# AmpClickShematic.net
KiCad netlist of a schematic drawn in Altium Designer
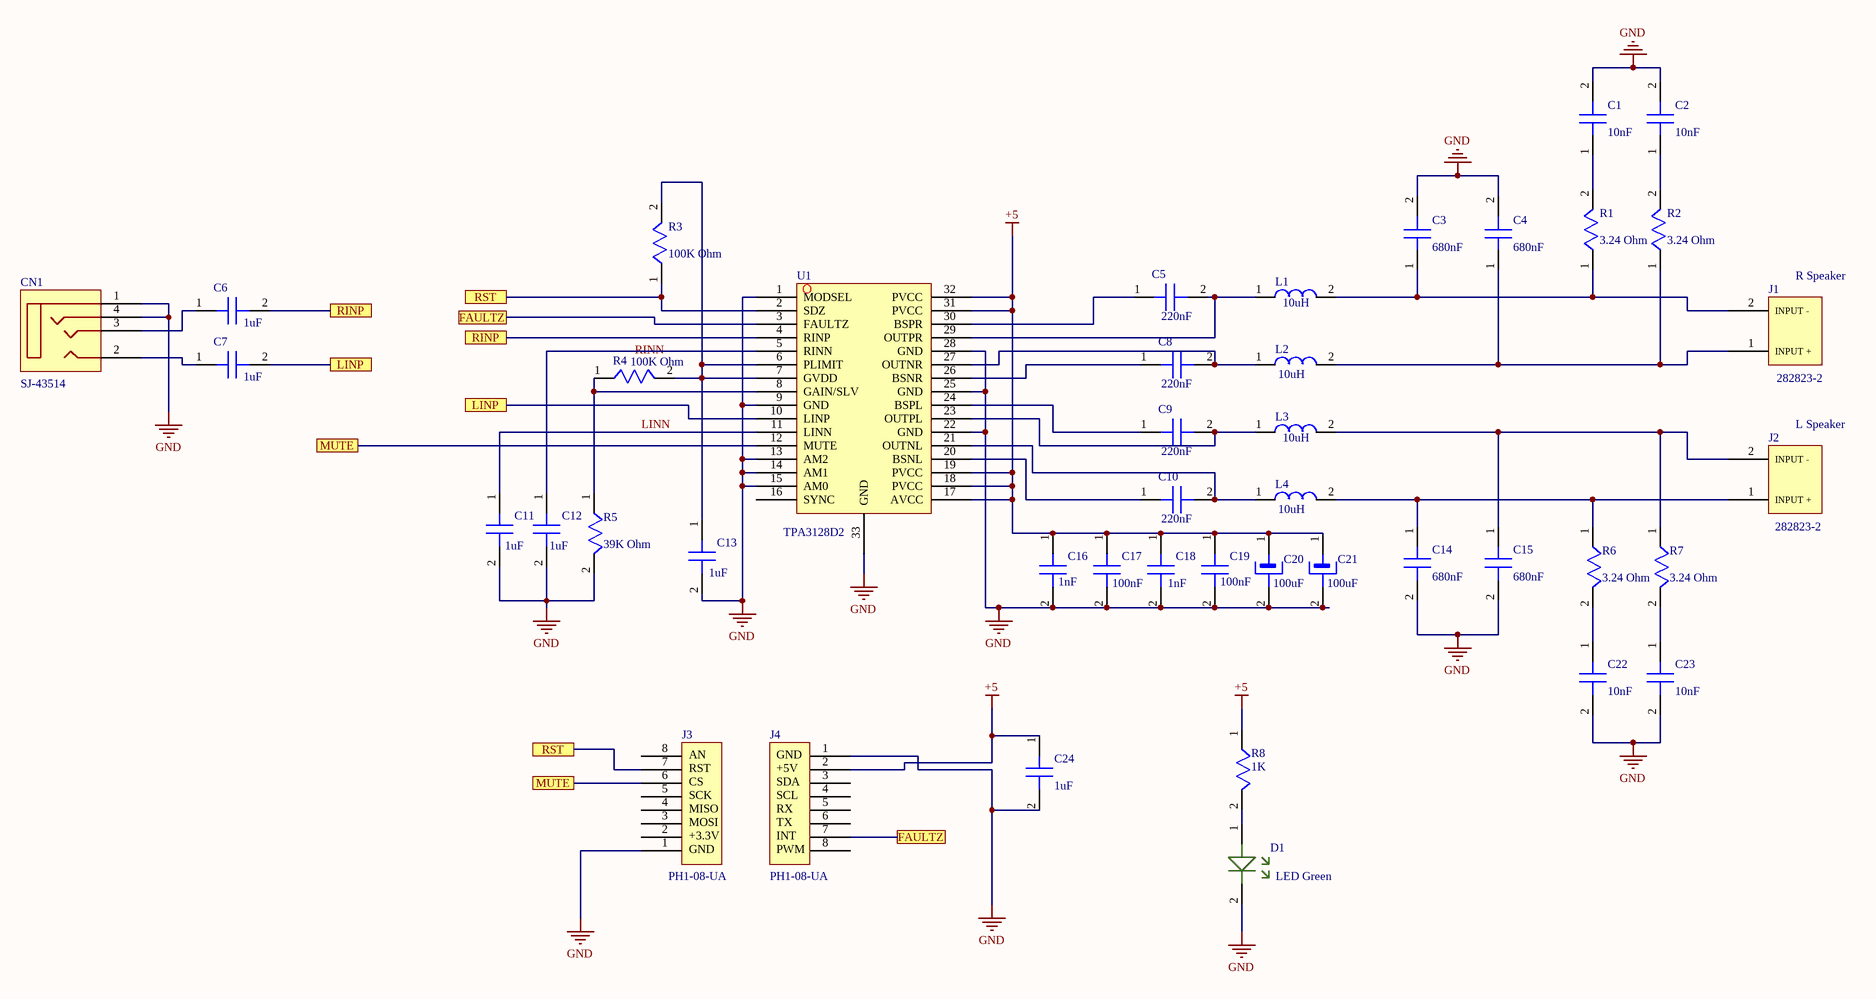
[diagram p0: AmpClickShematic.SchDoc]

(export (version "E")
  (design (tool "Eeschema 10.0.6"))
  (components
    (comp (ref "C1") (value "10nF") (footprint "CAP 10nF") (libsource (lib "AmpClick") (part "CAP 10nF")))
    (comp (ref "C2") (value "10nF") (footprint "CAP 10nF") (libsource (lib "AmpClick") (part "CAP 10nF")))
    (comp (ref "C3") (value "680nF") (footprint "CAP 680nF") (libsource (lib "AmpClick") (part "CAP 680nF")))
    (comp (ref "C4") (value "680nF") (footprint "CAP 680nF") (libsource (lib "AmpClick") (part "CAP 680nF")))
    (comp (ref "C5") (value "220nF") (footprint "CAP 220nF") (libsource (lib "AmpClick") (part "CAP 220nF")))
    (comp (ref "C6") (value "1uF") (footprint "CAP 1uF") (libsource (lib "AmpClick") (part "CAP 1uF")))
    (comp (ref "C7") (value "1uF") (footprint "CAP 1uF") (libsource (lib "AmpClick") (part "CAP 1uF")))
    (comp (ref "C8") (value "220nF") (footprint "CAP 220nF") (libsource (lib "AmpClick") (part "CAP 220nF")))
    (comp (ref "C9") (value "220nF") (footprint "CAP 220nF") (libsource (lib "AmpClick") (part "CAP 220nF")))
    (comp (ref "C10") (value "220nF") (footprint "CAP 220nF") (libsource (lib "AmpClick") (part "CAP 220nF")))
    (comp (ref "C11") (value "1uF") (footprint "CAP 1uF") (libsource (lib "AmpClick") (part "CAP 1uF")))
    (comp (ref "C12") (value "1uF") (footprint "CAP 1uF") (libsource (lib "AmpClick") (part "CAP 1uF")))
    (comp (ref "C13") (value "1uF") (footprint "CAP 1uF") (libsource (lib "AmpClick") (part "CAP 1uF")))
    (comp (ref "C14") (value "680nF") (footprint "CAP 680nF") (libsource (lib "AmpClick") (part "CAP 680nF")))
    (comp (ref "C15") (value "680nF") (footprint "CAP 680nF") (libsource (lib "AmpClick") (part "CAP 680nF")))
    (comp (ref "C16") (value "1nF") (footprint "CAP 1nF") (libsource (lib "AmpClick") (part "CAP 1nF")))
    (comp (ref "C17") (value "100nF") (footprint "CAP 100nF") (libsource (lib "AmpClick") (part "CAP 100nF")))
    (comp (ref "C18") (value "1nF") (footprint "CAP 1nF") (libsource (lib "AmpClick") (part "CAP 1nF")))
    (comp (ref "C19") (value "100nF") (footprint "CAP 100nF") (libsource (lib "AmpClick") (part "CAP 100nF")))
    (comp (ref "C20")
      (value "100uF")
      (footprint "CAP ALUM 100uF")
      (libsource (lib "AmpClick") (part "CAP ALUM 100uF"))
    )
    (comp (ref "C21")
      (value "100uF")
      (footprint "CAP ALUM 100uF")
      (libsource (lib "AmpClick") (part "CAP ALUM 100uF"))
    )
    (comp (ref "C22") (value "10nF") (footprint "CAP 10nF") (libsource (lib "AmpClick") (part "CAP 10nF")))
    (comp (ref "C23") (value "10nF") (footprint "CAP 10nF") (libsource (lib "AmpClick") (part "CAP 10nF")))
    (comp (ref "C24") (value "1uF") (footprint "CAP 1uF") (libsource (lib "AmpClick") (part "CAP 1uF")))
    (comp (ref "CN1")
      (value "Audio Jack")
      (footprint "Audio Jack")
      (fields (field (name "NAME") "SJ-43514"))
      (libsource (lib "AmpClick") (part "Audio Jack"))
    )
    (comp (ref "D1")
      (value "Green")
      (footprint "LED Green")
      (fields (field (name "NAME") "LED Green"))
      (libsource (lib "AmpClick") (part "LED Green"))
    )
    (comp (ref "J1")
      (value "R Speaker")
      (footprint "2P CONN 2.54mm")
      (fields (field (name "NAME") "282823-2"))
      (libsource (lib "AmpClick") (part "2P CONN"))
    )
    (comp (ref "J2")
      (value "L Speaker")
      (footprint "2P CONN 2.54mm")
      (fields (field (name "NAME") "282823-2"))
      (libsource (lib "AmpClick") (part "2P CONN"))
    )
    (comp (ref "J3")
      (value "8P HEADER")
      (footprint "8POS HEADER")
      (description "8 Position Header")
      (fields (field (name "NAME") "PH1-08-UA"))
      (libsource (lib "") (part "8P HEADER_1"))
    )
    (comp (ref "J4")
      (value "8P HEADER")
      (footprint "8POS HEADER")
      (description "8 Position Header")
      (fields (field (name "NAME") "PH1-08-UA"))
      (libsource (lib "AmpClick") (part "8P HEADER"))
    )
    (comp (ref "L1")
      (value "10uH")
      (footprint "Power Inductor")
      (fields (field (name "Comment") "Power Inductor 10uH"))
      (libsource (lib "AmpClick") (part "Power Inductor 10uH"))
    )
    (comp (ref "L2")
      (value "10uH")
      (footprint "Power Inductor")
      (fields (field (name "Comment") "Power Inductor 10uH"))
      (libsource (lib "AmpClick") (part "Power Inductor 10uH"))
    )
    (comp (ref "L3")
      (value "10uH")
      (footprint "Power Inductor")
      (fields (field (name "Comment") "Power Inductor 10uH"))
      (libsource (lib "AmpClick") (part "Power Inductor 10uH"))
    )
    (comp (ref "L4")
      (value "10uH")
      (footprint "Power Inductor")
      (fields (field (name "Comment") "Power Inductor 10uH"))
      (libsource (lib "AmpClick") (part "Power Inductor 10uH"))
    )
    (comp (ref "R1")
      (value "3.24 Ohm")
      (footprint "SMD RES 3.24ohm")
      (fields (field (name "Comment") "3.24ohm"))
      (libsource (lib "AmpClick") (part "SMD RES 3.24OHM"))
    )
    (comp (ref "R2")
      (value "3.24 Ohm")
      (footprint "SMD RES 3.24ohm")
      (fields (field (name "Comment") "3.24ohm"))
      (libsource (lib "AmpClick") (part "SMD RES 3.24OHM"))
    )
    (comp (ref "R3")
      (value "100K Ohm")
      (footprint "SMD RES 100K")
      (fields (field (name "Comment") "100K"))
      (libsource (lib "AmpClick") (part "SMD RES 100K"))
    )
    (comp (ref "R4")
      (value "100K Ohm")
      (footprint "SMD RES 100K")
      (fields (field (name "Comment") "100K"))
      (libsource (lib "AmpClick") (part "SMD RES 100K"))
    )
    (comp (ref "R5")
      (value "39K Ohm")
      (footprint "SMD RES 39K")
      (fields (field (name "Comment") "SMD RES 39K"))
      (libsource (lib "AmpClick") (part "SMD RES 39K"))
    )
    (comp (ref "R6")
      (value "3.24 Ohm")
      (footprint "SMD RES 3.24ohm")
      (fields (field (name "Comment") "3.24ohm"))
      (libsource (lib "AmpClick") (part "SMD RES 3.24OHM"))
    )
    (comp (ref "R7")
      (value "3.24 Ohm")
      (footprint "SMD RES 3.24ohm")
      (fields (field (name "Comment") "3.24ohm"))
      (libsource (lib "AmpClick") (part "SMD RES 3.24OHM"))
    )
    (comp (ref "R8") (value "1K") (footprint "SMD RES 1K") (libsource (lib "AmpClick") (part "SMD RES 1K")))
    (comp (ref "U1")
      (value "TPA 30W AMP.")
      (footprint "TPA 30W AMP.")
      (description "TPA 2x30W IC")
      (fields (field (name "NAME") "TPA3128D2"))
      (libsource (lib "AmpClick") (part "TPA 30W AMP."))
    )
  )
  (nets
    (net (code "1") (name "+5") (class "Default")
      (node (ref "C16") (pin "1") (pinfunction "PVCC_1") (pintype "passive"))
      (node (ref "C17") (pin "1") (pinfunction "PVCC_1") (pintype "passive"))
      (node (ref "C18") (pin "1") (pinfunction "PVCC_1") (pintype "passive"))
      (node (ref "C19") (pin "1") (pinfunction "PVCC_1") (pintype "passive"))
      (node (ref "C20") (pin "1") (pinfunction "PVCC_1") (pintype "passive"))
      (node (ref "C21") (pin "1") (pinfunction "PVCC_1") (pintype "passive"))
      (node (ref "C24") (pin "1") (pinfunction "PVCC_1") (pintype "passive"))
      (node (ref "J4") (pin "2") (pinfunction "6_2") (pintype "passive"))
      (node (ref "R8") (pin "1") (pinfunction "0_1") (pintype "passive"))
      (node (ref "U1") (pin "17") (pinfunction "AVCC_17") (pintype "passive"))
      (node (ref "U1") (pin "18") (pinfunction "PVCC_18") (pintype "passive"))
      (node (ref "U1") (pin "19") (pinfunction "PVCC_19") (pintype "passive"))
      (node (ref "U1") (pin "31") (pinfunction "PVCC_31") (pintype "passive"))
      (node (ref "U1") (pin "32") (pinfunction "PVCC_32") (pintype "passive"))
    )
    (net (code "2") (name "/FAULTZ") (class "Default")
      (node (ref "J4") (pin "7") (pinfunction "11_7") (pintype "passive"))
      (node (ref "U1") (pin "3") (pinfunction "FAULTZ_3") (pintype "passive"))
    )
    (net (code "3") (name "/LINP") (class "Default")
      (node (ref "C7") (pin "2") (pinfunction "PVCC_2") (pintype "passive"))
      (node (ref "U1") (pin "10") (pinfunction "LINP_10") (pintype "passive"))
    )
    (net (code "4") (name "/MUTE") (class "Default")
      (node (ref "J3") (pin "6") (pinfunction "10_6") (pintype "passive"))
      (node (ref "U1") (pin "12") (pinfunction "MUTE_12") (pintype "passive"))
    )
    (net (code "5") (name "/RINP") (class "Default")
      (node (ref "C6") (pin "2") (pinfunction "PVCC_2") (pintype "passive"))
      (node (ref "U1") (pin "4") (pinfunction "RINP_4") (pintype "passive"))
    )
    (net (code "6") (name "/RST") (class "Default")
      (node (ref "J3") (pin "7") (pinfunction "11_7") (pintype "passive"))
      (node (ref "R3") (pin "1") (pinfunction "0_1") (pintype "passive"))
      (node (ref "U1") (pin "2") (pinfunction "SDZ_2") (pintype "passive"))
    )
    (net (code "7") (name "GND") (class "Default")
      (node (ref "C1") (pin "2") (pinfunction "PVCC_2") (pintype "passive"))
      (node (ref "C11") (pin "2") (pinfunction "PVCC_2") (pintype "passive"))
      (node (ref "C12") (pin "2") (pinfunction "PVCC_2") (pintype "passive"))
      (node (ref "C13") (pin "2") (pinfunction "PVCC_2") (pintype "passive"))
      (node (ref "C14") (pin "2") (pinfunction "PVCC_2") (pintype "passive"))
      (node (ref "C15") (pin "2") (pinfunction "PVCC_2") (pintype "passive"))
      (node (ref "C16") (pin "2") (pinfunction "PVCC_2") (pintype "passive"))
      (node (ref "C17") (pin "2") (pinfunction "PVCC_2") (pintype "passive"))
      (node (ref "C18") (pin "2") (pinfunction "PVCC_2") (pintype "passive"))
      (node (ref "C19") (pin "2") (pinfunction "PVCC_2") (pintype "passive"))
      (node (ref "C2") (pin "2") (pinfunction "PVCC_2") (pintype "passive"))
      (node (ref "C20") (pin "2") (pinfunction "PVCC_2") (pintype "passive"))
      (node (ref "C21") (pin "2") (pinfunction "PVCC_2") (pintype "passive"))
      (node (ref "C22") (pin "2") (pinfunction "PVCC_2") (pintype "passive"))
      (node (ref "C23") (pin "2") (pinfunction "PVCC_2") (pintype "passive"))
      (node (ref "C24") (pin "2") (pinfunction "PVCC_2") (pintype "passive"))
      (node (ref "C3") (pin "2") (pinfunction "PVCC_2") (pintype "passive"))
      (node (ref "C4") (pin "2") (pinfunction "PVCC_2") (pintype "passive"))
      (node (ref "CN1") (pin "1") (pinfunction "5_1") (pintype "passive"))
      (node (ref "CN1") (pin "4") (pinfunction "6_4") (pintype "passive"))
      (node (ref "D1") (pin "2") (pinfunction "PVCC_2") (pintype "passive"))
      (node (ref "J3") (pin "1") (pinfunction "5_1") (pintype "passive"))
      (node (ref "J4") (pin "1") (pinfunction "5_1") (pintype "passive"))
      (node (ref "R5") (pin "2") (pinfunction "1_2") (pintype "passive"))
      (node (ref "U1") (pin "1") (pinfunction "MODSEL_1") (pintype "passive"))
      (node (ref "U1") (pin "13") (pinfunction "AM2_13") (pintype "passive"))
      (node (ref "U1") (pin "14") (pinfunction "AM1_14") (pintype "passive"))
      (node (ref "U1") (pin "15") (pinfunction "AM0_15") (pintype "passive"))
      (node (ref "U1") (pin "22") (pinfunction "GND_22") (pintype "passive"))
      (node (ref "U1") (pin "25") (pinfunction "GND_25") (pintype "passive"))
      (node (ref "U1") (pin "28") (pinfunction "GND_28") (pintype "passive"))
      (node (ref "U1") (pin "33") (pinfunction "GND_33") (pintype "passive"))
      (node (ref "U1") (pin "9") (pinfunction "GND_9") (pintype "passive"))
    )
    (net (code "8") (name "Net-(CN1-7)") (class "Default")
      (node (ref "C6") (pin "1") (pinfunction "PVCC_1") (pintype "passive"))
      (node (ref "CN1") (pin "3") (pinfunction "7_3") (pintype "passive"))
    )
    (net (code "9") (name "Net-(CN1-8)") (class "Default")
      (node (ref "C7") (pin "1") (pinfunction "PVCC_1") (pintype "passive"))
      (node (ref "CN1") (pin "2") (pinfunction "8_2") (pintype "passive"))
    )
    (net (code "10") (name "Net-(J1-INPUT_+)") (class "Default")
      (node (ref "C4") (pin "1") (pinfunction "PVCC_1") (pintype "passive"))
      (node (ref "J1") (pin "1") (pinfunction "INPUT_+_1") (pintype "passive"))
      (node (ref "L2") (pin "2") (pinfunction "2_2") (pintype "passive"))
      (node (ref "R2") (pin "1") (pinfunction "0_1") (pintype "passive"))
    )
    (net (code "11") (name "Net-(J1-INPUT_-)") (class "Default")
      (node (ref "C3") (pin "1") (pinfunction "PVCC_1") (pintype "passive"))
      (node (ref "J1") (pin "2") (pinfunction "INPUT_-_2") (pintype "passive"))
      (node (ref "L1") (pin "2") (pinfunction "2_2") (pintype "passive"))
      (node (ref "R1") (pin "1") (pinfunction "0_1") (pintype "passive"))
    )
    (net (code "12") (name "Net-(J2-INPUT_+)") (class "Default")
      (node (ref "C14") (pin "1") (pinfunction "PVCC_1") (pintype "passive"))
      (node (ref "J2") (pin "1") (pinfunction "INPUT_+_1") (pintype "passive"))
      (node (ref "L4") (pin "2") (pinfunction "2_2") (pintype "passive"))
      (node (ref "R6") (pin "1") (pinfunction "0_1") (pintype "passive"))
    )
    (net (code "13") (name "Net-(J2-INPUT_-)") (class "Default")
      (node (ref "C15") (pin "1") (pinfunction "PVCC_1") (pintype "passive"))
      (node (ref "J2") (pin "2") (pinfunction "INPUT_-_2") (pintype "passive"))
      (node (ref "L3") (pin "2") (pinfunction "2_2") (pintype "passive"))
      (node (ref "R7") (pin "1") (pinfunction "0_1") (pintype "passive"))
    )
    (net (code "14") (name "Net-(L1-15)") (class "Default")
      (node (ref "C5") (pin "2") (pinfunction "PVCC_2") (pintype "passive"))
      (node (ref "L1") (pin "1") (pinfunction "15_1") (pintype "passive"))
      (node (ref "U1") (pin "29") (pinfunction "OUTPR_29") (pintype "passive"))
    )
    (net (code "15") (name "Net-(L2-15)") (class "Default")
      (node (ref "C8") (pin "2") (pinfunction "PVCC_2") (pintype "passive"))
      (node (ref "L2") (pin "1") (pinfunction "15_1") (pintype "passive"))
      (node (ref "U1") (pin "27") (pinfunction "OUTNR_27") (pintype "passive"))
    )
    (net (code "16") (name "Net-(L3-15)") (class "Default")
      (node (ref "C9") (pin "2") (pinfunction "PVCC_2") (pintype "passive"))
      (node (ref "L3") (pin "1") (pinfunction "15_1") (pintype "passive"))
      (node (ref "U1") (pin "23") (pinfunction "OUTPL_23") (pintype "passive"))
    )
    (net (code "17") (name "Net-(L4-15)") (class "Default")
      (node (ref "C10") (pin "2") (pinfunction "PVCC_2") (pintype "passive"))
      (node (ref "L4") (pin "1") (pinfunction "15_1") (pintype "passive"))
      (node (ref "U1") (pin "21") (pinfunction "OUTNL_21") (pintype "passive"))
    )
    (net (code "18") (name "Net-(R1-1)") (class "Default")
      (node (ref "C1") (pin "1") (pinfunction "PVCC_1") (pintype "passive"))
      (node (ref "R1") (pin "2") (pinfunction "1_2") (pintype "passive"))
    )
    (net (code "19") (name "Net-(R2-1)") (class "Default")
      (node (ref "C2") (pin "1") (pinfunction "PVCC_1") (pintype "passive"))
      (node (ref "R2") (pin "2") (pinfunction "1_2") (pintype "passive"))
    )
    (net (code "20") (name "Net-(R3-1)") (class "Default")
      (node (ref "C13") (pin "1") (pinfunction "PVCC_1") (pintype "passive"))
      (node (ref "R3") (pin "2") (pinfunction "1_2") (pintype "passive"))
      (node (ref "R4") (pin "2") (pinfunction "1_2") (pintype "passive"))
      (node (ref "U1") (pin "6") (pinfunction "PLIMIT_6") (pintype "passive"))
      (node (ref "U1") (pin "7") (pinfunction "GVDD_7") (pintype "passive"))
    )
    (net (code "21") (name "Net-(R4-0)") (class "Default")
      (node (ref "R4") (pin "1") (pinfunction "0_1") (pintype "passive"))
      (node (ref "R5") (pin "1") (pinfunction "0_1") (pintype "passive"))
      (node (ref "U1") (pin "8") (pinfunction "GAIN/SLV_8") (pintype "passive"))
    )
    (net (code "22") (name "Net-(R6-1)") (class "Default")
      (node (ref "C22") (pin "1") (pinfunction "PVCC_1") (pintype "passive"))
      (node (ref "R6") (pin "2") (pinfunction "1_2") (pintype "passive"))
    )
    (net (code "23") (name "Net-(R7-1)") (class "Default")
      (node (ref "C23") (pin "1") (pinfunction "PVCC_1") (pintype "passive"))
      (node (ref "R7") (pin "2") (pinfunction "1_2") (pintype "passive"))
    )
    (net (code "24") (name "Net-(R8-1)") (class "Default")
      (node (ref "D1") (pin "1") (pinfunction "PVCC_1") (pintype "passive"))
      (node (ref "R8") (pin "2") (pinfunction "1_2") (pintype "passive"))
    )
    (net (code "25") (name "Net-(U1-BSNL)") (class "Default")
      (node (ref "C10") (pin "1") (pinfunction "PVCC_1") (pintype "passive"))
      (node (ref "U1") (pin "20") (pinfunction "BSNL_20") (pintype "passive"))
    )
    (net (code "26") (name "Net-(U1-BSNR)") (class "Default")
      (node (ref "C8") (pin "1") (pinfunction "PVCC_1") (pintype "passive"))
      (node (ref "U1") (pin "26") (pinfunction "BSNR_26") (pintype "passive"))
    )
    (net (code "27") (name "Net-(U1-BSPL)") (class "Default")
      (node (ref "C9") (pin "1") (pinfunction "PVCC_1") (pintype "passive"))
      (node (ref "U1") (pin "24") (pinfunction "BSPL_24") (pintype "passive"))
    )
    (net (code "28") (name "Net-(U1-BSPR)") (class "Default")
      (node (ref "C5") (pin "1") (pinfunction "PVCC_1") (pintype "passive"))
      (node (ref "U1") (pin "30") (pinfunction "BSPR_30") (pintype "passive"))
    )
    (net (code "29") (name "Net-(U1-LINN)") (class "Default")
      (node (ref "C11") (pin "1") (pinfunction "PVCC_1") (pintype "passive"))
      (node (ref "U1") (pin "11") (pinfunction "LINN_11") (pintype "passive"))
    )
    (net (code "30") (name "Net-(U1-RINN)") (class "Default")
      (node (ref "C12") (pin "1") (pinfunction "PVCC_1") (pintype "passive"))
      (node (ref "U1") (pin "5") (pinfunction "RINN_5") (pintype "passive"))
    )
    (net (code "31") (name "unconnected-(J3-6-Pad2)") (class "Default")
      (node (ref "J3") (pin "2") (pinfunction "6_2") (pintype "passive"))
    )
    (net (code "32") (name "unconnected-(J3-7-Pad3)") (class "Default")
      (node (ref "J3") (pin "3") (pinfunction "7_3") (pintype "passive"))
    )
    (net (code "33") (name "unconnected-(J3-8-Pad4)") (class "Default")
      (node (ref "J3") (pin "4") (pinfunction "8_4") (pintype "passive"))
    )
    (net (code "34") (name "unconnected-(J3-9-Pad5)") (class "Default")
      (node (ref "J3") (pin "5") (pinfunction "9_5") (pintype "passive"))
    )
    (net (code "35") (name "unconnected-(J3-12-Pad8)") (class "Default")
      (node (ref "J3") (pin "8") (pinfunction "12_8") (pintype "passive"))
    )
    (net (code "36") (name "unconnected-(J4-7-Pad3)") (class "Default")
      (node (ref "J4") (pin "3") (pinfunction "7_3") (pintype "passive"))
    )
    (net (code "37") (name "unconnected-(J4-8-Pad4)") (class "Default")
      (node (ref "J4") (pin "4") (pinfunction "8_4") (pintype "passive"))
    )
    (net (code "38") (name "unconnected-(J4-9-Pad5)") (class "Default")
      (node (ref "J4") (pin "5") (pinfunction "9_5") (pintype "passive"))
    )
    (net (code "39") (name "unconnected-(J4-10-Pad6)") (class "Default")
      (node (ref "J4") (pin "6") (pinfunction "10_6") (pintype "passive"))
    )
    (net (code "40") (name "unconnected-(J4-12-Pad8)") (class "Default")
      (node (ref "J4") (pin "8") (pinfunction "12_8") (pintype "passive"))
    )
    (net (code "41") (name "unconnected-(U1-SYNC-Pad16)") (class "Default")
      (node (ref "U1") (pin "16") (pinfunction "SYNC_16") (pintype "passive"))
    )
  )
)
